# queso_dip_v100.net
KiCad netlist of a schematic drawn in EAGLE
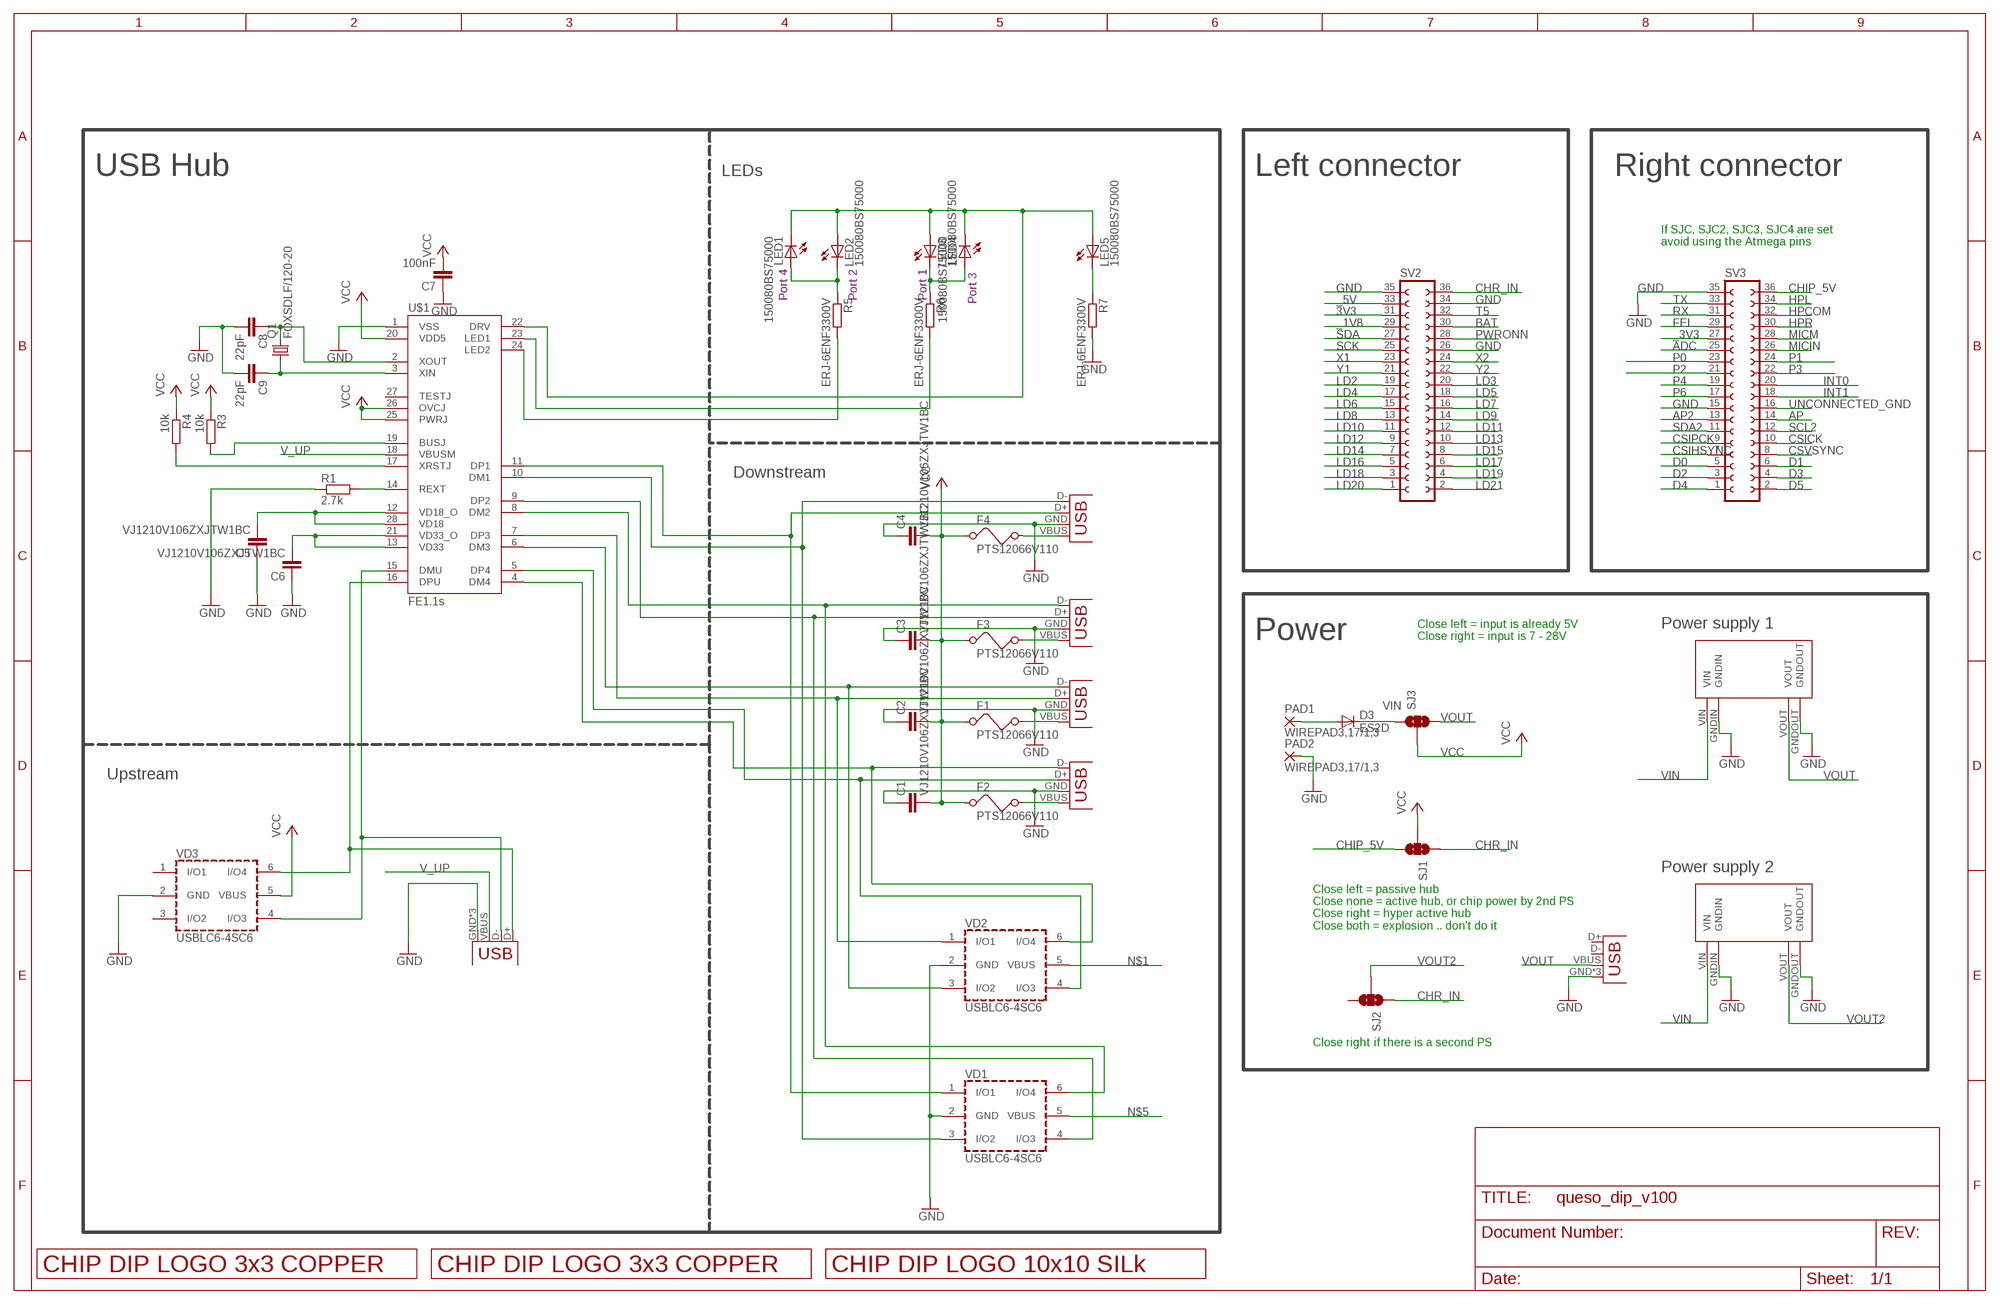
[diagram p0: schematic, sheet 1]

(export (version "E")
  (design (tool "Eeschema 10.0.6"))
  (components
    (comp (ref "C1")
      (value "VJ1210V106ZXJTW1BC")
      (footprint "eagle-import:C1210")
      (libsource (lib "eagle-import") (part "C-EUC1210"))
    )
    (comp (ref "C2")
      (value "VJ1210V106ZXJTW1BC")
      (footprint "eagle-import:C1210")
      (libsource (lib "eagle-import") (part "C-EUC1210"))
    )
    (comp (ref "C3")
      (value "VJ1210V106ZXJTW1BC")
      (footprint "eagle-import:C1210")
      (libsource (lib "eagle-import") (part "C-EUC1210"))
    )
    (comp (ref "C4")
      (value "VJ1210V106ZXJTW1BC")
      (footprint "eagle-import:C1210")
      (libsource (lib "eagle-import") (part "C-EUC1210"))
    )
    (comp (ref "C5")
      (value "VJ1210V106ZXJTW1BC")
      (footprint "eagle-import:C1210")
      (libsource (lib "eagle-import") (part "C-EUC1210"))
    )
    (comp (ref "C6")
      (value "VJ1210V106ZXJTW1BC")
      (footprint "eagle-import:C1210")
      (libsource (lib "eagle-import") (part "C-EUC1210"))
    )
    (comp (ref "C7")
      (value "100nF")
      (footprint "eagle-import:C0805")
      (libsource (lib "eagle-import") (part "C-EUC0805"))
    )
    (comp (ref "C8")
      (value "22pF")
      (footprint "eagle-import:C0805")
      (libsource (lib "eagle-import") (part "C-EUC0805"))
    )
    (comp (ref "C9")
      (value "22pF")
      (footprint "eagle-import:C0805")
      (libsource (lib "eagle-import") (part "C-EUC0805"))
    )
    (comp (ref "D3")
      (value "ES2D")
      (footprint "eagle-import:SMB")
      (libsource (lib "eagle-import") (part "ES2D"))
    )
    (comp (ref "DATA_USB")
      (value "USBUSB-MICROB-SMT-DIP")
      (footprint "eagle-import:USB-MICROB-SMT-DIP")
      (libsource (lib "eagle-import") (part "USBUSB-MICROB-SMT-DIP"))
    )
    (comp (ref "F1")
      (value "PTS12066V110")
      (footprint "eagle-import:1210")
      (libsource (lib "eagle-import") (part "FUSED"))
    )
    (comp (ref "F2")
      (value "PTS12066V110")
      (footprint "eagle-import:1210")
      (libsource (lib "eagle-import") (part "FUSED"))
    )
    (comp (ref "F3")
      (value "PTS12066V110")
      (footprint "eagle-import:1210")
      (libsource (lib "eagle-import") (part "FUSED"))
    )
    (comp (ref "F4")
      (value "PTS12066V110")
      (footprint "eagle-import:1210")
      (libsource (lib "eagle-import") (part "FUSED"))
    )
    (comp (ref "LED1")
      (value "150080BS75000")
      (footprint "eagle-import:CHIP-LED0805")
      (libsource (lib "eagle-import") (part "LEDCHIP-LED0805"))
    )
    (comp (ref "LED2")
      (value "150080BS75000")
      (footprint "eagle-import:CHIP-LED0805")
      (libsource (lib "eagle-import") (part "LEDCHIP-LED0805"))
    )
    (comp (ref "LED3")
      (value "150080BS75000")
      (footprint "eagle-import:CHIP-LED0805")
      (libsource (lib "eagle-import") (part "LEDCHIP-LED0805"))
    )
    (comp (ref "LED4")
      (value "150080BS75000")
      (footprint "eagle-import:CHIP-LED0805")
      (libsource (lib "eagle-import") (part "LEDCHIP-LED0805"))
    )
    (comp (ref "LED5")
      (value "150080BS75000")
      (footprint "eagle-import:CHIP-LED0805")
      (libsource (lib "eagle-import") (part "LEDCHIP-LED0805"))
    )
    (comp (ref "PAD1")
      (value "WIREPAD3,17/1,3")
      (footprint "eagle-import:3,17_1,3")
      (libsource (lib "eagle-import") (part "WIREPAD3,17/1,3"))
    )
    (comp (ref "PAD2")
      (value "WIREPAD3,17/1,3")
      (footprint "eagle-import:3,17_1,3")
      (libsource (lib "eagle-import") (part "WIREPAD3,17/1,3"))
    )
    (comp (ref "POWER_USB")
      (value "USBUSB-MICROB-SMT-DIP")
      (footprint "eagle-import:USB-MICROB-SMT-DIP")
      (libsource (lib "eagle-import") (part "USBUSB-MICROB-SMT-DIP"))
    )
    (comp (ref "Q1")
      (value "FOXSDLF/120-20")
      (footprint "eagle-import:SM49")
      (libsource (lib "eagle-import") (part "CRYSTALSM49"))
    )
    (comp (ref "R1")
      (value "2.7k")
      (footprint "eagle-import:R0805")
      (libsource (lib "eagle-import") (part "R-EU_R0805"))
    )
    (comp (ref "R3")
      (value "10k")
      (footprint "eagle-import:R0805")
      (libsource (lib "eagle-import") (part "R-EU_R0805"))
    )
    (comp (ref "R4")
      (value "10k")
      (footprint "eagle-import:R0805")
      (libsource (lib "eagle-import") (part "R-EU_R0805"))
    )
    (comp (ref "R5")
      (value "ERJ-6ENF3300V")
      (footprint "eagle-import:R0805")
      (libsource (lib "eagle-import") (part "R-EU_R0805"))
    )
    (comp (ref "R6")
      (value "ERJ-6ENF3300V")
      (footprint "eagle-import:R0805")
      (libsource (lib "eagle-import") (part "R-EU_R0805"))
    )
    (comp (ref "R7")
      (value "ERJ-6ENF3300V")
      (footprint "eagle-import:R0805")
      (libsource (lib "eagle-import") (part "R-EU_R0805"))
    )
    (comp (ref "SJ1")
      (value "SOLDERJUMPER_2WAYT")
      (footprint "eagle-import:SJ_2")
      (libsource (lib "eagle-import") (part "SOLDERJUMPER_2WAYT"))
    )
    (comp (ref "SJ2")
      (value "SOLDERJUMPER_2WAYT")
      (footprint "eagle-import:SJ_2")
      (libsource (lib "eagle-import") (part "SOLDERJUMPER_2WAYT"))
    )
    (comp (ref "SJ3")
      (value "SOLDERJUMPER_2WAYT")
      (footprint "eagle-import:SJ_2")
      (libsource (lib "eagle-import") (part "SOLDERJUMPER_2WAYT"))
    )
    (comp (ref "SV2")
      (value "FE18-2")
      (footprint "eagle-import:FE18-2")
      (libsource (lib "eagle-import") (part "FE18-2"))
    )
    (comp (ref "SV3")
      (value "FE18-2")
      (footprint "eagle-import:FE18-2")
      (libsource (lib "eagle-import") (part "FE18-2"))
    )
    (comp (ref "U$1")
      (value "FE1.1S")
      (footprint "eagle-import:FE1.1S_SSOP-28")
      (libsource (lib "eagle-import") (part "FE1.1S"))
    )
    (comp (ref "U$2")
      (value "LOGO_3X3_COPPER")
      (footprint "eagle-import:LOGO_3X3_COPPER")
      (libsource (lib "eagle-import") (part "LOGO_3X3_COPPER"))
    )
    (comp (ref "U$3")
      (value "MP1584EN")
      (footprint "eagle-import:MP1584EN")
      (libsource (lib "eagle-import") (part "MP1584EN"))
    )
    (comp (ref "U$4")
      (value "LOGO_3X3_COPPER")
      (footprint "eagle-import:LOGO_3X3_COPPER")
      (libsource (lib "eagle-import") (part "LOGO_3X3_COPPER"))
    )
    (comp (ref "U$5")
      (value "LOGO_10X10_SILK")
      (footprint "eagle-import:LOGO_10X10_SILK")
      (libsource (lib "eagle-import") (part "LOGO_10X10_SILK"))
    )
    (comp (ref "U$9")
      (value "MP1584EN")
      (footprint "eagle-import:MP1584EN")
      (libsource (lib "eagle-import") (part "MP1584EN"))
    )
    (comp (ref "VD1")
      (value "USBLC6-4SC6")
      (footprint "eagle-import:SOT-23-6L")
      (libsource (lib "eagle-import") (part "USBLC6-4SC6"))
    )
    (comp (ref "VD2")
      (value "USBLC6-4SC6")
      (footprint "eagle-import:SOT-23-6L")
      (libsource (lib "eagle-import") (part "USBLC6-4SC6"))
    )
    (comp (ref "VD3")
      (value "USBLC6-4SC6")
      (footprint "eagle-import:SOT-23-6L")
      (libsource (lib "eagle-import") (part "USBLC6-4SC6"))
    )
    (comp (ref "X1")
      (value "USB-A-HU")
      (footprint "eagle-import:USB-A-HU")
      (libsource (lib "eagle-import") (part "USB-A-HU"))
    )
    (comp (ref "X2")
      (value "USB-A-HU")
      (footprint "eagle-import:USB-A-HU")
      (libsource (lib "eagle-import") (part "USB-A-HU"))
    )
    (comp (ref "X3")
      (value "USB-A-HU")
      (footprint "eagle-import:USB-A-HU")
      (libsource (lib "eagle-import") (part "USB-A-HU"))
    )
    (comp (ref "X4")
      (value "USB-A-HU")
      (footprint "eagle-import:USB-A-HU")
      (libsource (lib "eagle-import") (part "USB-A-HU"))
    )
  )
  (nets
    (net (code "1") (name "/3V3") (class "Default")
      (node (ref "SV2") (pin "31") (pinfunction "31_31") (pintype "passive"))
    )
    (net (code "2") (name "/ADC") (class "Default")
      (node (ref "SV3") (pin "25") (pinfunction "25_25") (pintype "passive"))
    )
    (net (code "3") (name "/AP") (class "Default")
      (node (ref "SV3") (pin "14") (pinfunction "14_14") (pintype "passive"))
    )
    (net (code "4") (name "/AP2") (class "Default")
      (node (ref "SV3") (pin "13") (pinfunction "13_13") (pintype "passive"))
    )
    (net (code "5") (name "/BAT") (class "Default")
      (node (ref "SV2") (pin "30") (pinfunction "30_30") (pintype "passive"))
    )
    (net (code "6") (name "/CHIP_5V") (class "Default")
      (node (ref "SJ1") (pin "3") (pinfunction "3_3") (pintype "passive"))
      (node (ref "SV3") (pin "36") (pinfunction "36_36") (pintype "passive"))
    )
    (net (code "7") (name "/CHR_IN") (class "Default")
      (node (ref "SJ1") (pin "1") (pinfunction "1_1") (pintype "passive"))
      (node (ref "SJ2") (pin "1") (pinfunction "1_1") (pintype "passive"))
      (node (ref "SV2") (pin "36") (pinfunction "36_36") (pintype "passive"))
    )
    (net (code "8") (name "/CSICK") (class "Default")
      (node (ref "SV3") (pin "10") (pinfunction "10_10") (pintype "passive"))
    )
    (net (code "9") (name "/CSIHSYNC") (class "Default")
      (node (ref "SV3") (pin "7") (pinfunction "7_7") (pintype "passive"))
    )
    (net (code "10") (name "/CSIPCK") (class "Default")
      (node (ref "SV3") (pin "9") (pinfunction "9_9") (pintype "passive"))
    )
    (net (code "11") (name "/CSVSYNC") (class "Default")
      (node (ref "SV3") (pin "8") (pinfunction "8_8") (pintype "passive"))
    )
    (net (code "12") (name "/D0") (class "Default")
      (node (ref "SV3") (pin "5") (pinfunction "5_5") (pintype "passive"))
    )
    (net (code "13") (name "/D1") (class "Default")
      (node (ref "SV3") (pin "6") (pinfunction "6_6") (pintype "passive"))
    )
    (net (code "14") (name "/D2") (class "Default")
      (node (ref "SV3") (pin "3") (pinfunction "3_3") (pintype "passive"))
    )
    (net (code "15") (name "/D3") (class "Default")
      (node (ref "SV3") (pin "4") (pinfunction "4_4") (pintype "passive"))
    )
    (net (code "16") (name "/D4") (class "Default")
      (node (ref "SV3") (pin "1") (pinfunction "1_1") (pintype "passive"))
    )
    (net (code "17") (name "/D5") (class "Default")
      (node (ref "SV3") (pin "2") (pinfunction "2_2") (pintype "passive"))
    )
    (net (code "18") (name "/FEL") (class "Default")
      (node (ref "SV3") (pin "29") (pinfunction "29_29") (pintype "passive"))
    )
    (net (code "19") (name "/HPCOM") (class "Default")
      (node (ref "SV3") (pin "32") (pinfunction "32_32") (pintype "passive"))
    )
    (net (code "20") (name "/HPL") (class "Default")
      (node (ref "SV3") (pin "34") (pinfunction "34_34") (pintype "passive"))
    )
    (net (code "21") (name "/HPR") (class "Default")
      (node (ref "SV3") (pin "30") (pinfunction "30_30") (pintype "passive"))
    )
    (net (code "22") (name "/INT0") (class "Default")
      (node (ref "SV3") (pin "20") (pinfunction "20_20") (pintype "passive"))
    )
    (net (code "23") (name "/INT1") (class "Default")
      (node (ref "SV3") (pin "18") (pinfunction "18_18") (pintype "passive"))
    )
    (net (code "24") (name "/LD2") (class "Default")
      (node (ref "SV2") (pin "19") (pinfunction "19_19") (pintype "passive"))
    )
    (net (code "25") (name "/LD3") (class "Default")
      (node (ref "SV2") (pin "20") (pinfunction "20_20") (pintype "passive"))
    )
    (net (code "26") (name "/LD4") (class "Default")
      (node (ref "SV2") (pin "17") (pinfunction "17_17") (pintype "passive"))
    )
    (net (code "27") (name "/LD5") (class "Default")
      (node (ref "SV2") (pin "18") (pinfunction "18_18") (pintype "passive"))
    )
    (net (code "28") (name "/LD6") (class "Default")
      (node (ref "SV2") (pin "15") (pinfunction "15_15") (pintype "passive"))
    )
    (net (code "29") (name "/LD7") (class "Default")
      (node (ref "SV2") (pin "16") (pinfunction "16_16") (pintype "passive"))
    )
    (net (code "30") (name "/LD8") (class "Default")
      (node (ref "SV2") (pin "13") (pinfunction "13_13") (pintype "passive"))
    )
    (net (code "31") (name "/LD9") (class "Default")
      (node (ref "SV2") (pin "14") (pinfunction "14_14") (pintype "passive"))
    )
    (net (code "32") (name "/LD10") (class "Default")
      (node (ref "SV2") (pin "11") (pinfunction "11_11") (pintype "passive"))
    )
    (net (code "33") (name "/LD11") (class "Default")
      (node (ref "SV2") (pin "12") (pinfunction "12_12") (pintype "passive"))
    )
    (net (code "34") (name "/LD12") (class "Default")
      (node (ref "SV2") (pin "9") (pinfunction "9_9") (pintype "passive"))
    )
    (net (code "35") (name "/LD13") (class "Default")
      (node (ref "SV2") (pin "10") (pinfunction "10_10") (pintype "passive"))
    )
    (net (code "36") (name "/LD14") (class "Default")
      (node (ref "SV2") (pin "7") (pinfunction "7_7") (pintype "passive"))
    )
    (net (code "37") (name "/LD15") (class "Default")
      (node (ref "SV2") (pin "8") (pinfunction "8_8") (pintype "passive"))
    )
    (net (code "38") (name "/LD16") (class "Default")
      (node (ref "SV2") (pin "5") (pinfunction "5_5") (pintype "passive"))
    )
    (net (code "39") (name "/LD17") (class "Default")
      (node (ref "SV2") (pin "6") (pinfunction "6_6") (pintype "passive"))
    )
    (net (code "40") (name "/LD18") (class "Default")
      (node (ref "SV2") (pin "3") (pinfunction "3_3") (pintype "passive"))
    )
    (net (code "41") (name "/LD19") (class "Default")
      (node (ref "SV2") (pin "4") (pinfunction "4_4") (pintype "passive"))
    )
    (net (code "42") (name "/LD20") (class "Default")
      (node (ref "SV2") (pin "1") (pinfunction "1_1") (pintype "passive"))
    )
    (net (code "43") (name "/LD21") (class "Default")
      (node (ref "SV2") (pin "2") (pinfunction "2_2") (pintype "passive"))
    )
    (net (code "44") (name "/MICIN") (class "Default")
      (node (ref "SV3") (pin "26") (pinfunction "26_26") (pintype "passive"))
    )
    (net (code "45") (name "/MICM") (class "Default")
      (node (ref "SV3") (pin "28") (pinfunction "28_28") (pintype "passive"))
    )
    (net (code "46") (name "/N$1") (class "Default")
      (node (ref "F2") (pin "2") (pinfunction "2_2") (pintype "passive"))
      (node (ref "VD2") (pin "5") (pinfunction "VBUS_5") (pintype "bidirectional"))
      (node (ref "X1") (pin "VBUS") (pinfunction "GND_VBUS") (pintype "bidirectional"))
    )
    (net (code "47") (name "/N$5") (class "Default")
      (node (ref "F3") (pin "2") (pinfunction "2_2") (pintype "passive"))
      (node (ref "VD1") (pin "5") (pinfunction "VBUS_5") (pintype "bidirectional"))
      (node (ref "X3") (pin "VBUS") (pinfunction "GND_VBUS") (pintype "bidirectional"))
    )
    (net (code "48") (name "/P0") (class "Default")
      (node (ref "SV3") (pin "23") (pinfunction "23_23") (pintype "passive"))
    )
    (net (code "49") (name "/P1") (class "Default")
      (node (ref "SV3") (pin "24") (pinfunction "24_24") (pintype "passive"))
    )
    (net (code "50") (name "/P2") (class "Default")
      (node (ref "SV3") (pin "21") (pinfunction "21_21") (pintype "passive"))
    )
    (net (code "51") (name "/P3") (class "Default")
      (node (ref "SV3") (pin "22") (pinfunction "22_22") (pintype "passive"))
    )
    (net (code "52") (name "/P4") (class "Default")
      (node (ref "SV3") (pin "19") (pinfunction "19_19") (pintype "passive"))
    )
    (net (code "53") (name "/P6") (class "Default")
      (node (ref "SV3") (pin "17") (pinfunction "17_17") (pintype "passive"))
    )
    (net (code "54") (name "/PWRONN") (class "Default")
      (node (ref "SV2") (pin "28") (pinfunction "28_28") (pintype "passive"))
    )
    (net (code "55") (name "/RX") (class "Default")
      (node (ref "SV3") (pin "31") (pinfunction "31_31") (pintype "passive"))
    )
    (net (code "56") (name "/SCK") (class "Default")
      (node (ref "SV2") (pin "25") (pinfunction "25_25") (pintype "passive"))
    )
    (net (code "57") (name "/SCL2") (class "Default")
      (node (ref "SV3") (pin "12") (pinfunction "12_12") (pintype "passive"))
    )
    (net (code "58") (name "/SDA") (class "Default")
      (node (ref "SV2") (pin "27") (pinfunction "27_27") (pintype "passive"))
    )
    (net (code "59") (name "/SDA2") (class "Default")
      (node (ref "SV3") (pin "11") (pinfunction "11_11") (pintype "passive"))
    )
    (net (code "60") (name "/T5") (class "Default")
      (node (ref "SV2") (pin "32") (pinfunction "32_32") (pintype "passive"))
    )
    (net (code "61") (name "/TX") (class "Default")
      (node (ref "SV3") (pin "33") (pinfunction "33_33") (pintype "passive"))
    )
    (net (code "62") (name "/UNCONNECTED_GND") (class "Default")
      (node (ref "SV3") (pin "16") (pinfunction "16_16") (pintype "passive"))
    )
    (net (code "63") (name "/VIN") (class "Default")
      (node (ref "D3") (pin "C") (pinfunction "C_C") (pintype "passive"))
      (node (ref "SJ3") (pin "1") (pinfunction "1_1") (pintype "passive"))
      (node (ref "U$3") (pin "VIN") (pinfunction "VIN_VIN") (pintype "power_in"))
      (node (ref "U$9") (pin "VIN") (pinfunction "VIN_VIN") (pintype "power_in"))
    )
    (net (code "64") (name "/VOUT") (class "Default")
      (node (ref "POWER_USB") (pin "VBUS") (pinfunction "VBUS_VBUS") (pintype "bidirectional"))
      (node (ref "SJ3") (pin "3") (pinfunction "3_3") (pintype "passive"))
      (node (ref "U$9") (pin "VOUT") (pinfunction "VOUT_VOUT") (pintype "power_in"))
    )
    (net (code "65") (name "/VOUT2") (class "Default")
      (node (ref "SJ2") (pin "2") (pinfunction "2_2") (pintype "passive"))
      (node (ref "U$3") (pin "VOUT") (pinfunction "VOUT_VOUT") (pintype "power_in"))
    )
    (net (code "66") (name "/V_UP") (class "Default")
      (node (ref "DATA_USB") (pin "VBUS") (pinfunction "VBUS_VBUS") (pintype "bidirectional"))
      (node (ref "U$1") (pin "18") (pinfunction "VBUSM_18") (pintype "bidirectional"))
    )
    (net (code "67") (name "/X1") (class "Default")
      (node (ref "SV2") (pin "23") (pinfunction "23_23") (pintype "passive"))
    )
    (net (code "68") (name "/X2") (class "Default")
      (node (ref "SV2") (pin "24") (pinfunction "24_24") (pintype "passive"))
    )
    (net (code "69") (name "/Y1") (class "Default")
      (node (ref "SV2") (pin "21") (pinfunction "21_21") (pintype "passive"))
    )
    (net (code "70") (name "/Y2") (class "Default")
      (node (ref "SV2") (pin "22") (pinfunction "22_22") (pintype "passive"))
    )
    (net (code "71") (name "/_1V8") (class "Default")
      (node (ref "SV2") (pin "29") (pinfunction "29_29") (pintype "passive"))
    )
    (net (code "72") (name "/_3V3") (class "Default")
      (node (ref "SV3") (pin "27") (pinfunction "27_27") (pintype "passive"))
    )
    (net (code "73") (name "/_5V") (class "Default")
      (node (ref "SV2") (pin "33") (pinfunction "33_33") (pintype "passive"))
    )
    (net (code "74") (name "GND") (class "Default")
      (node (ref "C1") (pin "1") (pinfunction "1_1") (pintype "passive"))
      (node (ref "C2") (pin "1") (pinfunction "1_1") (pintype "passive"))
      (node (ref "C3") (pin "1") (pinfunction "1_1") (pintype "passive"))
      (node (ref "C4") (pin "1") (pinfunction "1_1") (pintype "passive"))
      (node (ref "C5") (pin "1") (pinfunction "1_1") (pintype "passive"))
      (node (ref "C6") (pin "1") (pinfunction "1_1") (pintype "passive"))
      (node (ref "C7") (pin "1") (pinfunction "1_1") (pintype "passive"))
      (node (ref "C8") (pin "2") (pinfunction "2_2") (pintype "passive"))
      (node (ref "C9") (pin "2") (pinfunction "2_2") (pintype "passive"))
      (node (ref "DATA_USB") (pin "GND") (pinfunction "GND_GND") (pintype "bidirectional"))
      (node (ref "DATA_USB") (pin "MT1") (pinfunction "GND_MT1") (pintype "bidirectional"))
      (node (ref "DATA_USB") (pin "MT2") (pinfunction "GND_MT2") (pintype "bidirectional"))
      (node (ref "PAD2") (pin "1") (pinfunction "P_1") (pintype "passive"))
      (node (ref "POWER_USB") (pin "GND") (pinfunction "GND_GND") (pintype "bidirectional"))
      (node (ref "POWER_USB") (pin "MT1") (pinfunction "GND_MT1") (pintype "bidirectional"))
      (node (ref "POWER_USB") (pin "MT2") (pinfunction "GND_MT2") (pintype "bidirectional"))
      (node (ref "R1") (pin "1") (pinfunction "1_1") (pintype "passive"))
      (node (ref "R7") (pin "2") (pinfunction "2_2") (pintype "passive"))
      (node (ref "SV2") (pin "26") (pinfunction "26_26") (pintype "passive"))
      (node (ref "SV2") (pin "34") (pinfunction "34_34") (pintype "passive"))
      (node (ref "SV2") (pin "35") (pinfunction "35_35") (pintype "passive"))
      (node (ref "SV3") (pin "15") (pinfunction "15_15") (pintype "passive"))
      (node (ref "SV3") (pin "35") (pinfunction "35_35") (pintype "passive"))
      (node (ref "U$1") (pin "1") (pinfunction "VSS_1") (pintype "bidirectional"))
      (node (ref "U$3") (pin "GNDIN") (pinfunction "GNDIN_GNDIN") (pintype "power_in"))
      (node (ref "U$3") (pin "GNDOUT") (pinfunction "GNDOUT_GNDOUT") (pintype "power_in"))
      (node (ref "U$9") (pin "GNDIN") (pinfunction "GNDIN_GNDIN") (pintype "power_in"))
      (node (ref "U$9") (pin "GNDOUT") (pinfunction "GNDOUT_GNDOUT") (pintype "power_in"))
      (node (ref "VD1") (pin "2") (pinfunction "GND_2") (pintype "bidirectional"))
      (node (ref "VD2") (pin "2") (pinfunction "GND_2") (pintype "bidirectional"))
      (node (ref "VD3") (pin "2") (pinfunction "GND_2") (pintype "bidirectional"))
      (node (ref "X1") (pin "GND") (pinfunction "VBUS_GND") (pintype "bidirectional"))
      (node (ref "X2") (pin "GND") (pinfunction "VBUS_GND") (pintype "bidirectional"))
      (node (ref "X3") (pin "GND") (pinfunction "VBUS_GND") (pintype "bidirectional"))
      (node (ref "X4") (pin "GND") (pinfunction "VBUS_GND") (pintype "bidirectional"))
    )
    (net (code "75") (name "Net-(LED1-PadA)") (class "Default")
      (node (ref "LED1") (pin "A") (pinfunction "A_A") (pintype "passive"))
      (node (ref "LED2") (pin "C") (pinfunction "C_C") (pintype "passive"))
      (node (ref "R5") (pin "1") (pinfunction "1_1") (pintype "passive"))
    )
    (net (code "76") (name "Net-(LED3-PadC)") (class "Default")
      (node (ref "LED3") (pin "C") (pinfunction "C_C") (pintype "passive"))
      (node (ref "LED4") (pin "A") (pinfunction "A_A") (pintype "passive"))
      (node (ref "R6") (pin "1") (pinfunction "1_1") (pintype "passive"))
    )
    (net (code "77") (name "Net-(LED5-PadC)") (class "Default")
      (node (ref "LED5") (pin "C") (pinfunction "C_C") (pintype "passive"))
      (node (ref "R7") (pin "1") (pinfunction "1_1") (pintype "passive"))
    )
    (net (code "78") (name "Net-(PAD1-P)") (class "Default")
      (node (ref "D3") (pin "A") (pinfunction "A_A") (pintype "passive"))
      (node (ref "PAD1") (pin "1") (pinfunction "P_1") (pintype "passive"))
    )
    (net (code "79") (name "Net-(U$1-BUSJ)") (class "Default")
      (node (ref "R3") (pin "2") (pinfunction "2_2") (pintype "passive"))
      (node (ref "U$1") (pin "19") (pinfunction "BUSJ_19") (pintype "bidirectional"))
    )
    (net (code "80") (name "Net-(U$1-DM1)") (class "Default")
      (node (ref "U$1") (pin "10") (pinfunction "DM1_10") (pintype "bidirectional"))
      (node (ref "VD1") (pin "3") (pinfunction "I/O2_3") (pintype "bidirectional"))
      (node (ref "X4") (pin "D-") (pinfunction "D+_D-") (pintype "bidirectional"))
    )
    (net (code "81") (name "Net-(U$1-DM2)") (class "Default")
      (node (ref "U$1") (pin "8") (pinfunction "DM2_8") (pintype "bidirectional"))
      (node (ref "VD1") (pin "6") (pinfunction "I/O4_6") (pintype "bidirectional"))
      (node (ref "X3") (pin "D-") (pinfunction "D+_D-") (pintype "bidirectional"))
    )
    (net (code "82") (name "Net-(U$1-DM3)") (class "Default")
      (node (ref "U$1") (pin "6") (pinfunction "DM3_6") (pintype "bidirectional"))
      (node (ref "VD2") (pin "3") (pinfunction "I/O2_3") (pintype "bidirectional"))
      (node (ref "X2") (pin "D-") (pinfunction "D+_D-") (pintype "bidirectional"))
    )
    (net (code "83") (name "Net-(U$1-DM4)") (class "Default")
      (node (ref "U$1") (pin "4") (pinfunction "DM4_4") (pintype "bidirectional"))
      (node (ref "VD2") (pin "6") (pinfunction "I/O4_6") (pintype "bidirectional"))
      (node (ref "X1") (pin "D-") (pinfunction "D+_D-") (pintype "bidirectional"))
    )
    (net (code "84") (name "Net-(U$1-DMU)") (class "Default")
      (node (ref "DATA_USB") (pin "D-") (pinfunction "D-_D-") (pintype "bidirectional"))
      (node (ref "U$1") (pin "15") (pinfunction "DMU_15") (pintype "bidirectional"))
      (node (ref "VD3") (pin "4") (pinfunction "I/O3_4") (pintype "bidirectional"))
    )
    (net (code "85") (name "Net-(U$1-DP1)") (class "Default")
      (node (ref "U$1") (pin "11") (pinfunction "DP1_11") (pintype "bidirectional"))
      (node (ref "VD1") (pin "1") (pinfunction "I/O1_1") (pintype "bidirectional"))
      (node (ref "X4") (pin "D+") (pinfunction "D-_D+") (pintype "bidirectional"))
    )
    (net (code "86") (name "Net-(U$1-DP2)") (class "Default")
      (node (ref "U$1") (pin "9") (pinfunction "DP2_9") (pintype "bidirectional"))
      (node (ref "VD1") (pin "4") (pinfunction "I/O3_4") (pintype "bidirectional"))
      (node (ref "X3") (pin "D+") (pinfunction "D-_D+") (pintype "bidirectional"))
    )
    (net (code "87") (name "Net-(U$1-DP3)") (class "Default")
      (node (ref "U$1") (pin "7") (pinfunction "DP3_7") (pintype "bidirectional"))
      (node (ref "VD2") (pin "1") (pinfunction "I/O1_1") (pintype "bidirectional"))
      (node (ref "X2") (pin "D+") (pinfunction "D-_D+") (pintype "bidirectional"))
    )
    (net (code "88") (name "Net-(U$1-DP4)") (class "Default")
      (node (ref "U$1") (pin "5") (pinfunction "DP4_5") (pintype "bidirectional"))
      (node (ref "VD2") (pin "4") (pinfunction "I/O3_4") (pintype "bidirectional"))
      (node (ref "X1") (pin "D+") (pinfunction "D-_D+") (pintype "bidirectional"))
    )
    (net (code "89") (name "Net-(U$1-DPU)") (class "Default")
      (node (ref "DATA_USB") (pin "D+") (pinfunction "D+_D+") (pintype "bidirectional"))
      (node (ref "U$1") (pin "16") (pinfunction "DPU_16") (pintype "bidirectional"))
      (node (ref "VD3") (pin "6") (pinfunction "I/O4_6") (pintype "bidirectional"))
    )
    (net (code "90") (name "Net-(U$1-DRV)") (class "Default")
      (node (ref "LED1") (pin "C") (pinfunction "C_C") (pintype "passive"))
      (node (ref "LED2") (pin "A") (pinfunction "A_A") (pintype "passive"))
      (node (ref "LED3") (pin "A") (pinfunction "A_A") (pintype "passive"))
      (node (ref "LED4") (pin "C") (pinfunction "C_C") (pintype "passive"))
      (node (ref "LED5") (pin "A") (pinfunction "A_A") (pintype "passive"))
      (node (ref "U$1") (pin "22") (pinfunction "DRV_22") (pintype "bidirectional"))
    )
    (net (code "91") (name "Net-(U$1-LED1)") (class "Default")
      (node (ref "R6") (pin "2") (pinfunction "2_2") (pintype "passive"))
      (node (ref "U$1") (pin "23") (pinfunction "LED1_23") (pintype "bidirectional"))
    )
    (net (code "92") (name "Net-(U$1-LED2)") (class "Default")
      (node (ref "R5") (pin "2") (pinfunction "2_2") (pintype "passive"))
      (node (ref "U$1") (pin "24") (pinfunction "LED2_24") (pintype "bidirectional"))
    )
    (net (code "93") (name "Net-(U$1-REXT)") (class "Default")
      (node (ref "R1") (pin "2") (pinfunction "2_2") (pintype "passive"))
      (node (ref "U$1") (pin "14") (pinfunction "REXT_14") (pintype "bidirectional"))
    )
    (net (code "94") (name "Net-(U$1-VD18)") (class "Default")
      (node (ref "C5") (pin "2") (pinfunction "2_2") (pintype "passive"))
      (node (ref "U$1") (pin "12") (pinfunction "VD18_O_12") (pintype "bidirectional"))
      (node (ref "U$1") (pin "28") (pinfunction "VD18_28") (pintype "bidirectional"))
    )
    (net (code "95") (name "Net-(U$1-VD33)") (class "Default")
      (node (ref "C6") (pin "2") (pinfunction "2_2") (pintype "passive"))
      (node (ref "U$1") (pin "13") (pinfunction "VD33_13") (pintype "bidirectional"))
      (node (ref "U$1") (pin "21") (pinfunction "VD33_O_21") (pintype "bidirectional"))
    )
    (net (code "96") (name "Net-(U$1-XIN)") (class "Default")
      (node (ref "C9") (pin "1") (pinfunction "1_1") (pintype "passive"))
      (node (ref "Q1") (pin "1") (pinfunction "1_1") (pintype "passive"))
      (node (ref "U$1") (pin "3") (pinfunction "XIN_3") (pintype "bidirectional"))
    )
    (net (code "97") (name "Net-(U$1-XOUT)") (class "Default")
      (node (ref "C8") (pin "1") (pinfunction "1_1") (pintype "passive"))
      (node (ref "Q1") (pin "2") (pinfunction "2_2") (pintype "passive"))
      (node (ref "U$1") (pin "2") (pinfunction "XOUT_2") (pintype "bidirectional"))
    )
    (net (code "98") (name "Net-(U$1-XRSTJ)") (class "Default")
      (node (ref "R4") (pin "2") (pinfunction "2_2") (pintype "passive"))
      (node (ref "U$1") (pin "17") (pinfunction "XRSTJ_17") (pintype "bidirectional"))
    )
    (net (code "99") (name "Net-(X2-GND)") (class "Default")
      (node (ref "F1") (pin "2") (pinfunction "2_2") (pintype "passive"))
      (node (ref "X2") (pin "VBUS") (pinfunction "GND_VBUS") (pintype "bidirectional"))
    )
    (net (code "100") (name "Net-(X4-GND)") (class "Default")
      (node (ref "F4") (pin "2") (pinfunction "2_2") (pintype "passive"))
      (node (ref "X4") (pin "VBUS") (pinfunction "GND_VBUS") (pintype "bidirectional"))
    )
    (net (code "101") (name "VCC") (class "Default")
      (node (ref "C1") (pin "2") (pinfunction "2_2") (pintype "passive"))
      (node (ref "C2") (pin "2") (pinfunction "2_2") (pintype "passive"))
      (node (ref "C3") (pin "2") (pinfunction "2_2") (pintype "passive"))
      (node (ref "C4") (pin "2") (pinfunction "2_2") (pintype "passive"))
      (node (ref "C7") (pin "2") (pinfunction "2_2") (pintype "passive"))
      (node (ref "F1") (pin "1") (pinfunction "1_1") (pintype "passive"))
      (node (ref "F2") (pin "1") (pinfunction "1_1") (pintype "passive"))
      (node (ref "F3") (pin "1") (pinfunction "1_1") (pintype "passive"))
      (node (ref "F4") (pin "1") (pinfunction "1_1") (pintype "passive"))
      (node (ref "R3") (pin "1") (pinfunction "1_1") (pintype "passive"))
      (node (ref "R4") (pin "1") (pinfunction "1_1") (pintype "passive"))
      (node (ref "SJ1") (pin "2") (pinfunction "2_2") (pintype "passive"))
      (node (ref "SJ3") (pin "2") (pinfunction "2_2") (pintype "passive"))
      (node (ref "U$1") (pin "20") (pinfunction "VDD5_20") (pintype "bidirectional"))
      (node (ref "U$1") (pin "25") (pinfunction "PWRJ_25") (pintype "bidirectional"))
      (node (ref "U$1") (pin "26") (pinfunction "OVCJ_26") (pintype "bidirectional"))
      (node (ref "VD3") (pin "5") (pinfunction "VBUS_5") (pintype "bidirectional"))
    )
    (net (code "102") (name "unconnected-(POWER_USB-PadD+)") (class "Default")
      (node (ref "POWER_USB") (pin "D+") (pinfunction "D+_D+") (pintype "bidirectional"))
    )
    (net (code "103") (name "unconnected-(POWER_USB-PadD-)") (class "Default")
      (node (ref "POWER_USB") (pin "D-") (pinfunction "D-_D-") (pintype "bidirectional"))
    )
    (net (code "104") (name "unconnected-(SJ2-Pad3)") (class "Default")
      (node (ref "SJ2") (pin "3") (pinfunction "3_3") (pintype "passive"))
    )
    (net (code "105") (name "unconnected-(U$1-TESTJ-Pad27)") (class "Default")
      (node (ref "U$1") (pin "27") (pinfunction "TESTJ_27") (pintype "bidirectional"))
    )
    (net (code "106") (name "unconnected-(VD3-I{slash}O1-Pad1)") (class "Default")
      (node (ref "VD3") (pin "1") (pinfunction "I/O1_1") (pintype "bidirectional"))
    )
    (net (code "107") (name "unconnected-(VD3-I{slash}O2-Pad3)") (class "Default")
      (node (ref "VD3") (pin "3") (pinfunction "I/O2_3") (pintype "bidirectional"))
    )
  )
)
